# main.net
KiCad netlist of a schematic drawn in EAGLE
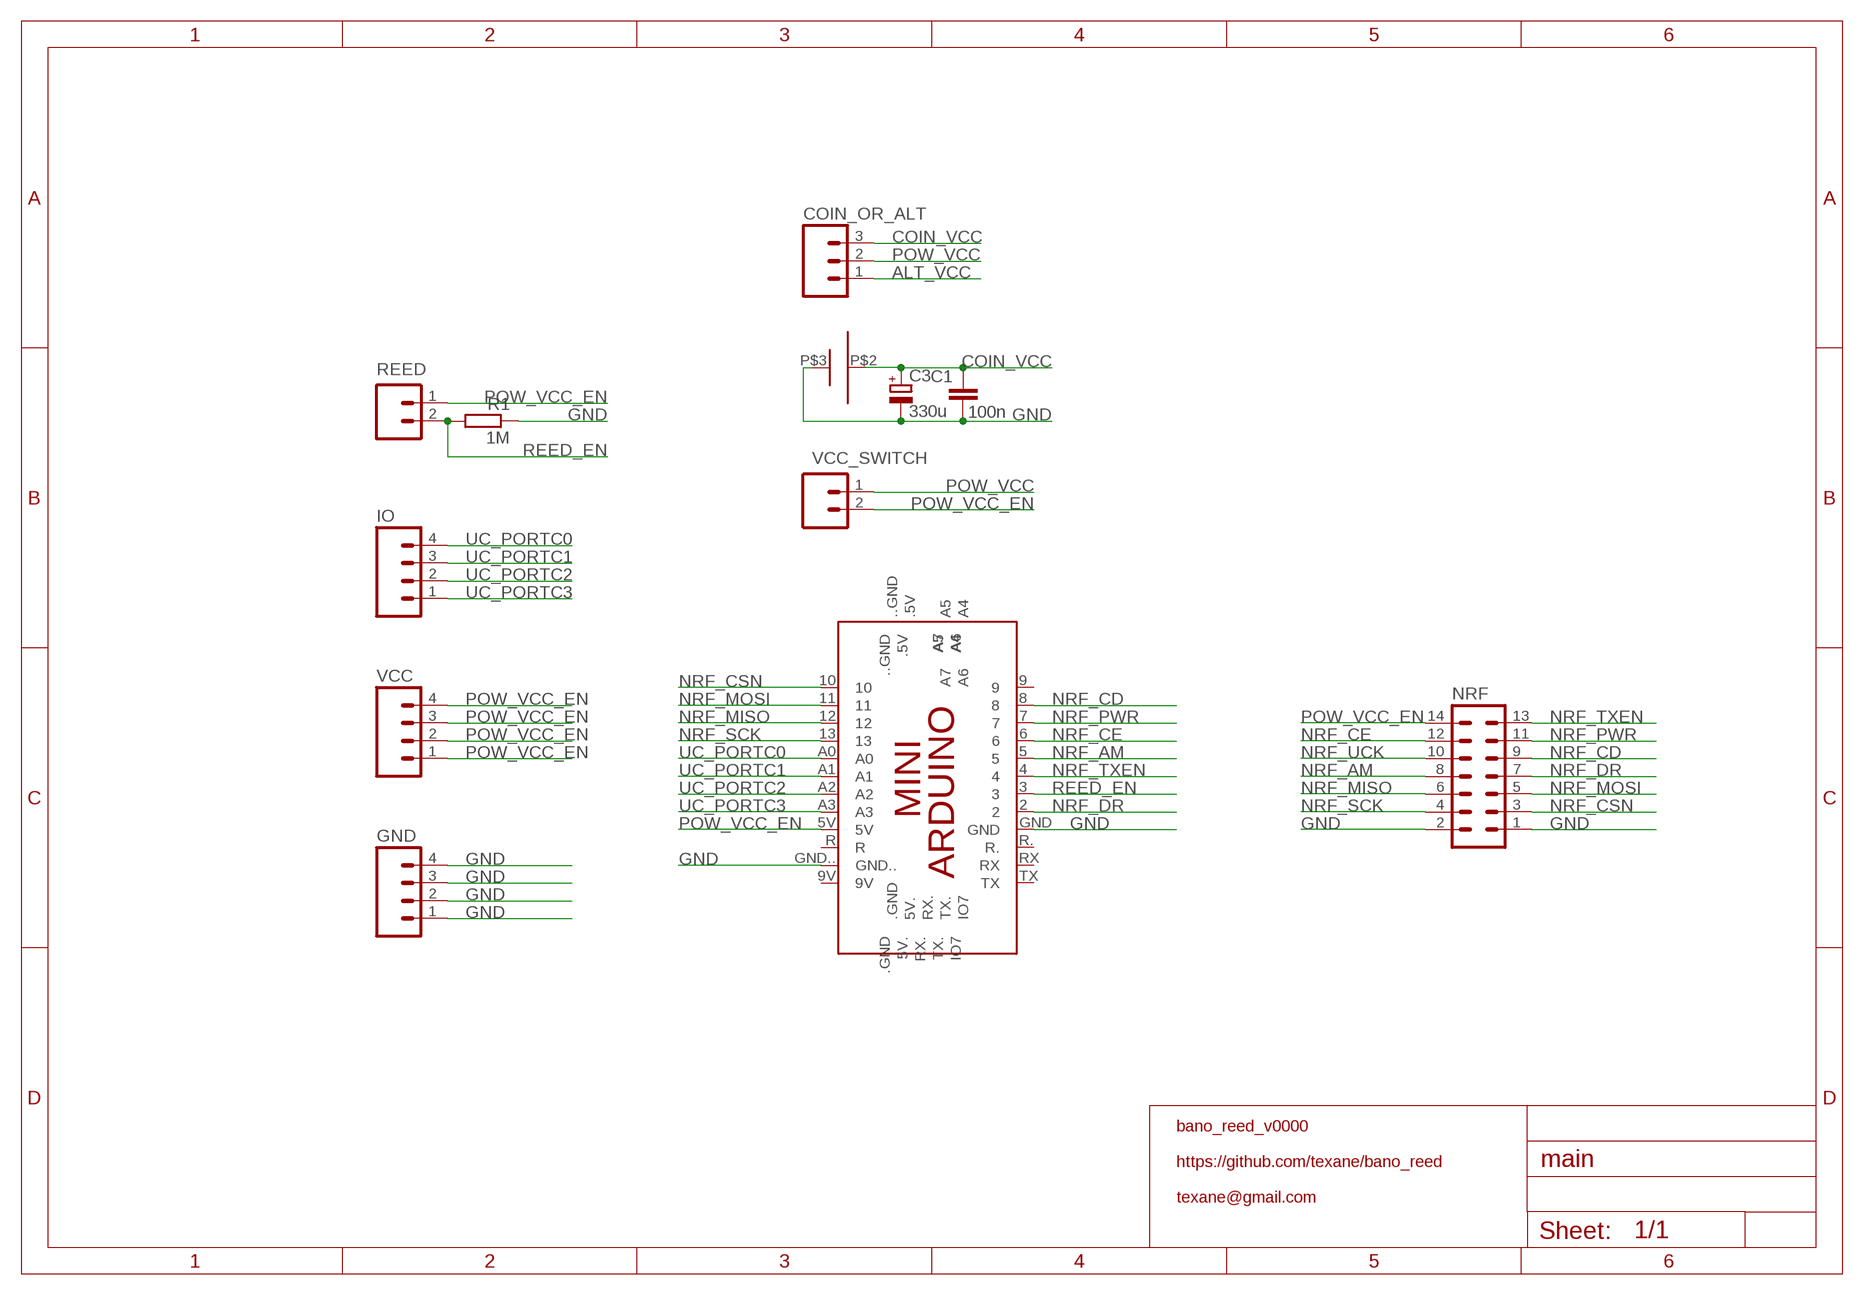
[diagram p0: schematic, sheet 1]

(export (version "E")
  (design (tool "Eeschema 10.0.6"))
  (components
    (comp (ref "C1")
      (value "100n")
      (footprint "eagle-import:C1206K")
      (libsource (lib "eagle-import") (part "C-EUC1206K"))
    )
    (comp (ref "C3")
      (value "330u")
      (footprint "eagle-import:PANASONIC_F")
      (libsource (lib "eagle-import") (part "CPOL-EUF"))
    )
    (comp (ref "COIN_OR_ALT")
      (value "M03PTH")
      (footprint "eagle-import:1X03")
      (libsource (lib "eagle-import") (part "M03PTH"))
    )
    (comp (ref "GND")
      (value "M04PTH")
      (footprint "eagle-import:1X04")
      (libsource (lib "eagle-import") (part "M04PTH"))
    )
    (comp (ref "IO")
      (value "M04PTH")
      (footprint "eagle-import:1X04")
      (libsource (lib "eagle-import") (part "M04PTH"))
    )
    (comp (ref "NRF")
      (value "MA07-2")
      (footprint "eagle-import:MA07-2")
      (libsource (lib "eagle-import") (part "MA07-2"))
    )
    (comp (ref "PCB1")
      (value "ARDUINO_MINI")
      (footprint "eagle-import:ARDUINO_MINI")
      (libsource (lib "eagle-import") (part "ARDUINO_MINI"))
    )
    (comp (ref "R1")
      (value "1M")
      (footprint "eagle-import:R1206")
      (libsource (lib "eagle-import") (part "R-EU_R1206"))
    )
    (comp (ref "REED")
      (value "M02PTH")
      (footprint "eagle-import:1X02")
      (libsource (lib "eagle-import") (part "M02PTH"))
    )
    (comp (ref "U$1")
      (value "KEYSTONE_1025_7")
      (footprint "eagle-import:KEYSTONE_1025_7")
      (libsource (lib "eagle-import") (part "KEYSTONE_1025_7"))
    )
    (comp (ref "VCC")
      (value "M04PTH")
      (footprint "eagle-import:1X04")
      (libsource (lib "eagle-import") (part "M04PTH"))
    )
    (comp (ref "VCC_SWITCH")
      (value "M02PTH")
      (footprint "eagle-import:1X02")
      (libsource (lib "eagle-import") (part "M02PTH"))
    )
  )
  (nets
    (net (code "1") (name "/ALT_VCC") (class "Default")
      (node (ref "COIN_OR_ALT") (pin "1") (pinfunction "1_1") (pintype "passive"))
    )
    (net (code "2") (name "/COIN_VCC") (class "Default")
      (node (ref "C1") (pin "1") (pinfunction "1_1") (pintype "passive"))
      (node (ref "C3") (pin "+") (pinfunction "+_+") (pintype "passive"))
      (node (ref "COIN_OR_ALT") (pin "3") (pinfunction "3_3") (pintype "passive"))
      (node (ref "U$1") (pin "P$2") (pinfunction "COIN_PLUS_P$2") (pintype "power_in"))
    )
    (net (code "3") (name "/GND") (class "Default")
      (node (ref "C1") (pin "2") (pinfunction "2_2") (pintype "passive"))
      (node (ref "C3") (pin "-") (pinfunction "-_-") (pintype "passive"))
      (node (ref "GND") (pin "1") (pinfunction "1_1") (pintype "passive"))
      (node (ref "GND") (pin "2") (pinfunction "2_2") (pintype "passive"))
      (node (ref "GND") (pin "3") (pinfunction "3_3") (pintype "passive"))
      (node (ref "GND") (pin "4") (pinfunction "4_4") (pintype "passive"))
      (node (ref "NRF") (pin "1") (pinfunction "1_1") (pintype "passive"))
      (node (ref "NRF") (pin "2") (pinfunction "2_2") (pintype "passive"))
      (node (ref "PCB1") (pin "GND") (pinfunction "GND_GND") (pintype "bidirectional"))
      (node (ref "PCB1") (pin "GND..") (pinfunction "GND.._GND..") (pintype "bidirectional"))
      (node (ref "R1") (pin "1") (pinfunction "1_1") (pintype "passive"))
      (node (ref "U$1") (pin "P$3") (pinfunction "COIN_MINUS_P$3") (pintype "power_in"))
    )
    (net (code "4") (name "/NRF_AM") (class "Default")
      (node (ref "NRF") (pin "8") (pinfunction "8_8") (pintype "passive"))
      (node (ref "PCB1") (pin "5") (pinfunction "5_5") (pintype "bidirectional"))
    )
    (net (code "5") (name "/NRF_CD") (class "Default")
      (node (ref "NRF") (pin "9") (pinfunction "9_9") (pintype "passive"))
      (node (ref "PCB1") (pin "8") (pinfunction "8_8") (pintype "bidirectional"))
    )
    (net (code "6") (name "/NRF_CE") (class "Default")
      (node (ref "NRF") (pin "12") (pinfunction "12_12") (pintype "passive"))
      (node (ref "PCB1") (pin "6") (pinfunction "6_6") (pintype "bidirectional"))
    )
    (net (code "7") (name "/NRF_CSN") (class "Default")
      (node (ref "NRF") (pin "3") (pinfunction "3_3") (pintype "passive"))
      (node (ref "PCB1") (pin "10") (pinfunction "10_10") (pintype "bidirectional"))
    )
    (net (code "8") (name "/NRF_DR") (class "Default")
      (node (ref "NRF") (pin "7") (pinfunction "7_7") (pintype "passive"))
      (node (ref "PCB1") (pin "2") (pinfunction "2_2") (pintype "bidirectional"))
    )
    (net (code "9") (name "/NRF_MISO") (class "Default")
      (node (ref "NRF") (pin "6") (pinfunction "6_6") (pintype "passive"))
      (node (ref "PCB1") (pin "12") (pinfunction "12_12") (pintype "bidirectional"))
    )
    (net (code "10") (name "/NRF_MOSI") (class "Default")
      (node (ref "NRF") (pin "5") (pinfunction "5_5") (pintype "passive"))
      (node (ref "PCB1") (pin "11") (pinfunction "11_11") (pintype "bidirectional"))
    )
    (net (code "11") (name "/NRF_PWR") (class "Default")
      (node (ref "NRF") (pin "11") (pinfunction "11_11") (pintype "passive"))
      (node (ref "PCB1") (pin "7") (pinfunction "7_7") (pintype "bidirectional"))
    )
    (net (code "12") (name "/NRF_SCK") (class "Default")
      (node (ref "NRF") (pin "4") (pinfunction "4_4") (pintype "passive"))
      (node (ref "PCB1") (pin "13") (pinfunction "13_13") (pintype "bidirectional"))
    )
    (net (code "13") (name "/NRF_TXEN") (class "Default")
      (node (ref "NRF") (pin "13") (pinfunction "13_13") (pintype "passive"))
      (node (ref "PCB1") (pin "4") (pinfunction "4_4") (pintype "bidirectional"))
    )
    (net (code "14") (name "/NRF_UCK") (class "Default")
      (node (ref "NRF") (pin "10") (pinfunction "10_10") (pintype "passive"))
    )
    (net (code "15") (name "/POW_VCC") (class "Default")
      (node (ref "COIN_OR_ALT") (pin "2") (pinfunction "2_2") (pintype "passive"))
      (node (ref "VCC_SWITCH") (pin "1") (pinfunction "1_1") (pintype "passive"))
    )
    (net (code "16") (name "/POW_VCC_EN") (class "Default")
      (node (ref "NRF") (pin "14") (pinfunction "14_14") (pintype "passive"))
      (node (ref "PCB1") (pin "5V") (pinfunction "5V_5V") (pintype "bidirectional"))
      (node (ref "REED") (pin "1") (pinfunction "1_1") (pintype "passive"))
      (node (ref "VCC") (pin "1") (pinfunction "1_1") (pintype "passive"))
      (node (ref "VCC") (pin "2") (pinfunction "2_2") (pintype "passive"))
      (node (ref "VCC") (pin "3") (pinfunction "3_3") (pintype "passive"))
      (node (ref "VCC") (pin "4") (pinfunction "4_4") (pintype "passive"))
      (node (ref "VCC_SWITCH") (pin "2") (pinfunction "2_2") (pintype "passive"))
    )
    (net (code "17") (name "/REED_EN") (class "Default")
      (node (ref "PCB1") (pin "3") (pinfunction "3_3") (pintype "bidirectional"))
      (node (ref "R1") (pin "2") (pinfunction "2_2") (pintype "passive"))
      (node (ref "REED") (pin "2") (pinfunction "2_2") (pintype "passive"))
    )
    (net (code "18") (name "/UC_PORTC0") (class "Default")
      (node (ref "IO") (pin "4") (pinfunction "4_4") (pintype "passive"))
      (node (ref "PCB1") (pin "A0") (pinfunction "A0_A0") (pintype "bidirectional"))
    )
    (net (code "19") (name "/UC_PORTC1") (class "Default")
      (node (ref "IO") (pin "3") (pinfunction "3_3") (pintype "passive"))
      (node (ref "PCB1") (pin "A1") (pinfunction "A1_A1") (pintype "bidirectional"))
    )
    (net (code "20") (name "/UC_PORTC2") (class "Default")
      (node (ref "IO") (pin "2") (pinfunction "2_2") (pintype "passive"))
      (node (ref "PCB1") (pin "A2") (pinfunction "A2_A2") (pintype "bidirectional"))
    )
    (net (code "21") (name "/UC_PORTC3") (class "Default")
      (node (ref "IO") (pin "1") (pinfunction "1_1") (pintype "passive"))
      (node (ref "PCB1") (pin "A3") (pinfunction "A3_A3") (pintype "bidirectional"))
    )
    (net (code "22") (name "unconnected-(PCB1-Pad..GND)") (class "Default")
      (node (ref "PCB1") (pin "..GND") (pinfunction "..GND_..GND") (pintype "bidirectional"))
    )
    (net (code "23") (name "unconnected-(PCB1-Pad.5V)") (class "Default")
      (node (ref "PCB1") (pin ".5V") (pinfunction ".5V_.5V") (pintype "bidirectional"))
    )
    (net (code "24") (name "unconnected-(PCB1-Pad.GND)") (class "Default")
      (node (ref "PCB1") (pin ".GND") (pinfunction ".GND_.GND") (pintype "bidirectional"))
    )
    (net (code "25") (name "unconnected-(PCB1-Pad5V.)") (class "Default")
      (node (ref "PCB1") (pin "5V.") (pinfunction "5V._5V.") (pintype "bidirectional"))
    )
    (net (code "26") (name "unconnected-(PCB1-Pad9)") (class "Default")
      (node (ref "PCB1") (pin "9") (pinfunction "9_9") (pintype "bidirectional"))
    )
    (net (code "27") (name "unconnected-(PCB1-Pad9V)") (class "Default")
      (node (ref "PCB1") (pin "9V") (pinfunction "9V_9V") (pintype "bidirectional"))
    )
    (net (code "28") (name "unconnected-(PCB1-PadA4)") (class "Default")
      (node (ref "PCB1") (pin "A4") (pinfunction "A4_A4") (pintype "bidirectional"))
    )
    (net (code "29") (name "unconnected-(PCB1-PadA5)") (class "Default")
      (node (ref "PCB1") (pin "A5") (pinfunction "A5_A5") (pintype "bidirectional"))
    )
    (net (code "30") (name "unconnected-(PCB1-PadA6)") (class "Default")
      (node (ref "PCB1") (pin "A6") (pinfunction "A6_A6") (pintype "bidirectional"))
    )
    (net (code "31") (name "unconnected-(PCB1-PadA7)") (class "Default")
      (node (ref "PCB1") (pin "A7") (pinfunction "A7_A7") (pintype "bidirectional"))
    )
    (net (code "32") (name "unconnected-(PCB1-PadIO7)") (class "Default")
      (node (ref "PCB1") (pin "IO7") (pinfunction "IO7_IO7") (pintype "bidirectional"))
    )
    (net (code "33") (name "unconnected-(PCB1-PadR)") (class "Default")
      (node (ref "PCB1") (pin "R") (pinfunction "R_R") (pintype "bidirectional"))
    )
    (net (code "34") (name "unconnected-(PCB1-PadR.)") (class "Default")
      (node (ref "PCB1") (pin "R.") (pinfunction "R._R.") (pintype "bidirectional"))
    )
    (net (code "35") (name "unconnected-(PCB1-PadRX)") (class "Default")
      (node (ref "PCB1") (pin "RX") (pinfunction "RX_RX") (pintype "bidirectional"))
    )
    (net (code "36") (name "unconnected-(PCB1-PadRX.)") (class "Default")
      (node (ref "PCB1") (pin "RX.") (pinfunction "RX._RX.") (pintype "bidirectional"))
    )
    (net (code "37") (name "unconnected-(PCB1-PadTX)") (class "Default")
      (node (ref "PCB1") (pin "TX") (pinfunction "TX_TX") (pintype "bidirectional"))
    )
    (net (code "38") (name "unconnected-(PCB1-PadTX.)") (class "Default")
      (node (ref "PCB1") (pin "TX.") (pinfunction "TX._TX.") (pintype "bidirectional"))
    )
  )
)
